# working.net
KiCad netlist of a schematic drawn in EAGLE
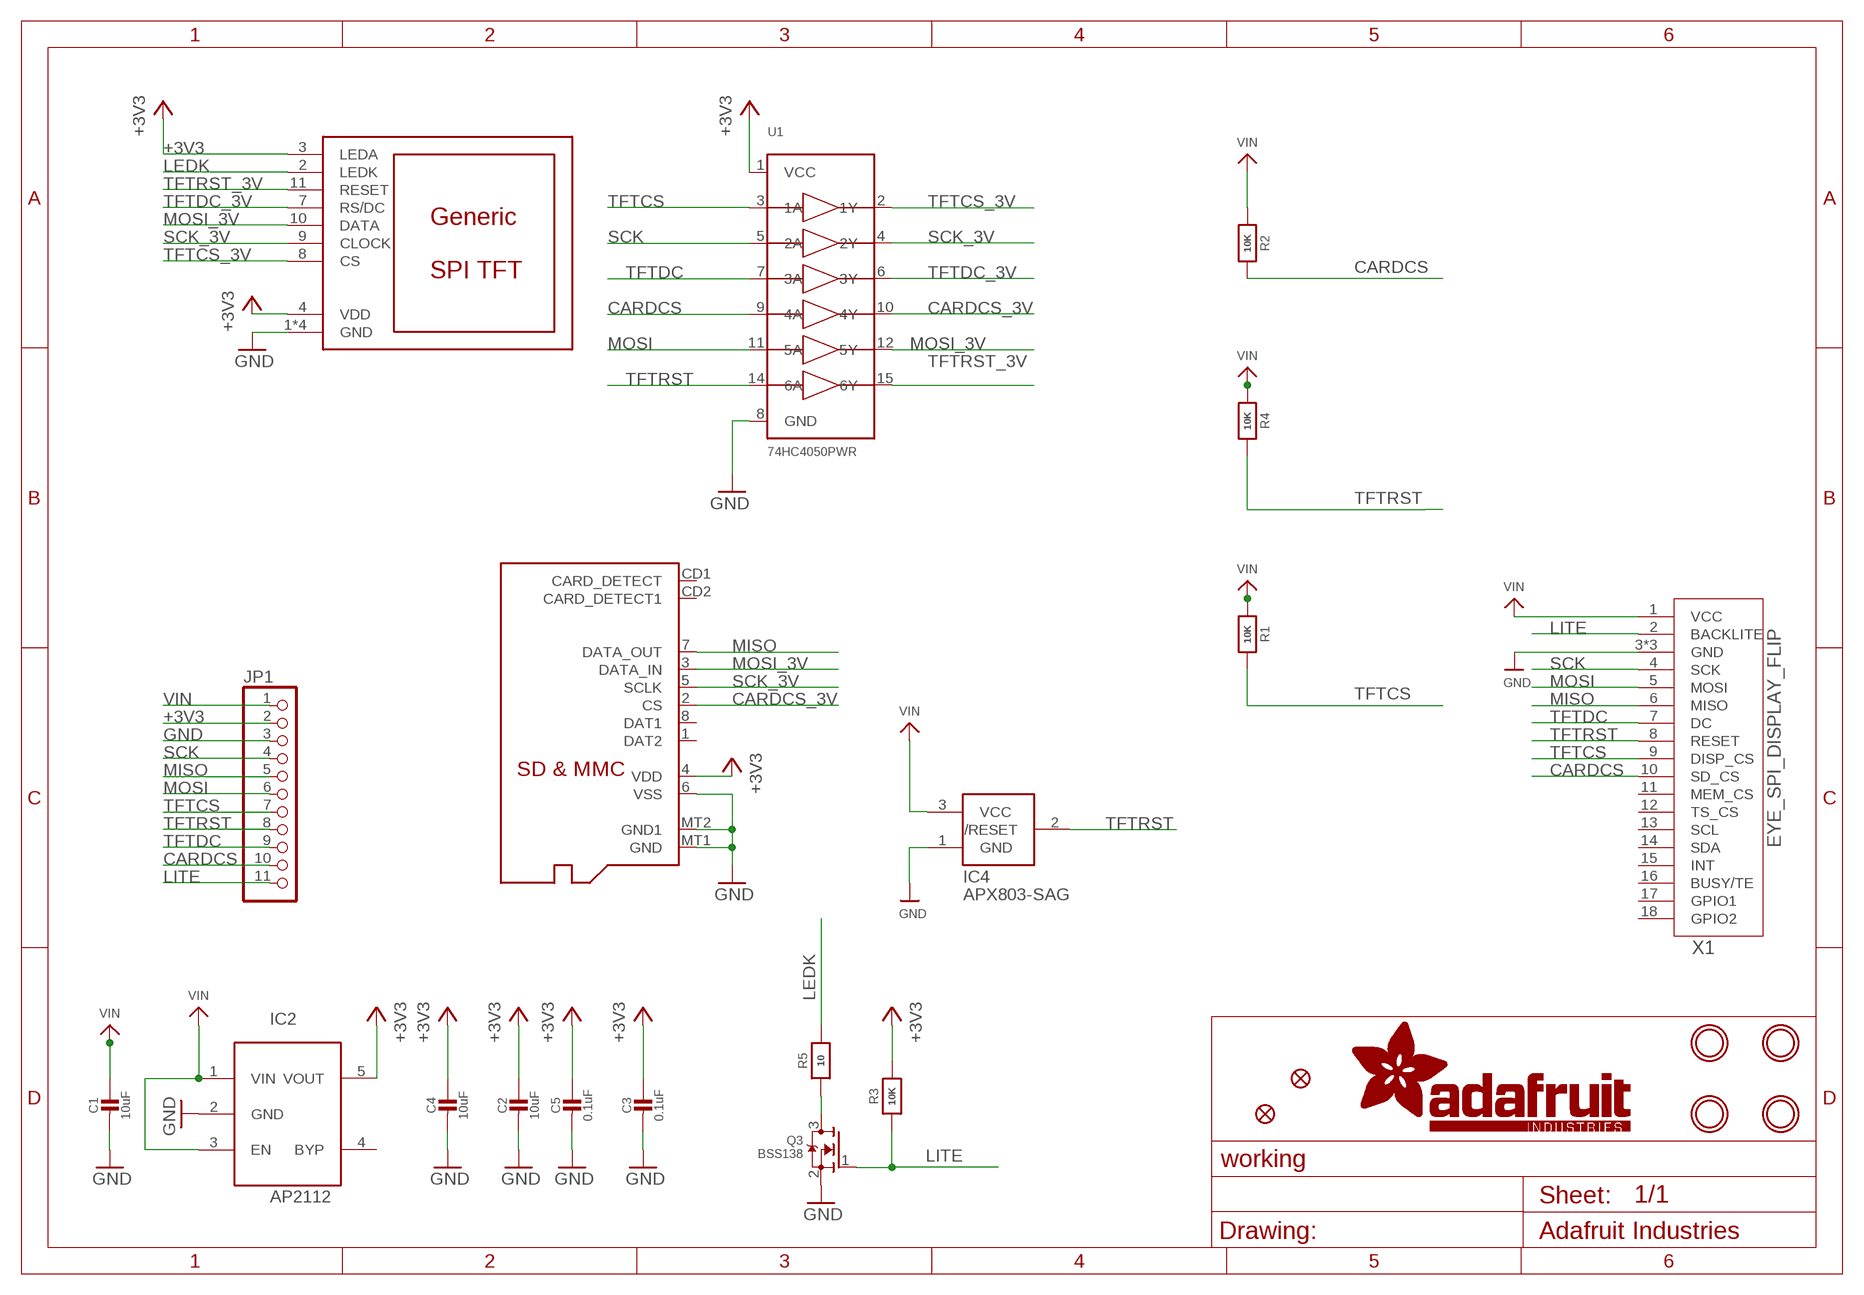
[diagram p0: schematic, sheet 1]

(export (version "E")
  (design (tool "Eeschema 10.0.6"))
  (components
    (comp (ref "C1")
      (value "10uF")
      (footprint "eagle-import:0805-NO")
      (libsource (lib "eagle-import") (part "CAP_CERAMIC0805-NOOUTLINE"))
    )
    (comp (ref "C2")
      (value "10uF")
      (footprint "eagle-import:0805-NO")
      (libsource (lib "eagle-import") (part "CAP_CERAMIC0805-NOOUTLINE"))
    )
    (comp (ref "C3")
      (value "0.1uF")
      (footprint "eagle-import:0603-NO")
      (libsource (lib "eagle-import") (part "CAP_CERAMIC0603_NO"))
    )
    (comp (ref "C4")
      (value "10uF")
      (footprint "eagle-import:0805-NO")
      (libsource (lib "eagle-import") (part "CAP_CERAMIC0805-NOOUTLINE"))
    )
    (comp (ref "C5")
      (value "0.1uF")
      (footprint "eagle-import:0603-NO")
      (libsource (lib "eagle-import") (part "CAP_CERAMIC0603_NO"))
    )
    (comp (ref "DISP1")
      (value "DISP_LCD_GENERIC_SPI_1.47IN_172X320_12P_WRAPUNDER")
      (footprint "eagle-import:TFT_1.47IN_172X320_12P")
      (libsource (lib "eagle-import") (part "DISP_LCD_GENERIC_SPI_1.47IN_172X320_12P_WRAPUNDER"))
    )
    (comp (ref "IC2")
      (value "AP2112")
      (footprint "eagle-import:SOT23-5L")
      (libsource (lib "eagle-import") (part "LP298XS"))
    )
    (comp (ref "IC4")
      (value "APX803-SAG")
      (footprint "eagle-import:SOT23")
      (libsource (lib "eagle-import") (part "AXP083-SAG"))
    )
    (comp (ref "JP1")
      (value "HEADER-1X1176MIL")
      (footprint "eagle-import:1X11_ROUND_76")
      (libsource (lib "eagle-import") (part "HEADER-1X1176MIL"))
    )
    (comp (ref "Q2")
      (value "MICROSD")
      (footprint "eagle-import:MICROSD")
      (libsource (lib "eagle-import") (part "MICROSD"))
    )
    (comp (ref "Q3")
      (value "BSS138")
      (footprint "eagle-import:SOT23-WIDE")
      (libsource (lib "eagle-import") (part "MOSFET-NWIDE"))
    )
    (comp (ref "R1")
      (value "10K")
      (footprint "eagle-import:0603-NO")
      (libsource (lib "eagle-import") (part "RESISTOR_0603_NOOUT"))
    )
    (comp (ref "R2")
      (value "10K")
      (footprint "eagle-import:0603-NO")
      (libsource (lib "eagle-import") (part "RESISTOR_0603_NOOUT"))
    )
    (comp (ref "R3")
      (value "10K")
      (footprint "eagle-import:0603-NO")
      (libsource (lib "eagle-import") (part "RESISTOR_0603_NOOUT"))
    )
    (comp (ref "R4")
      (value "10K")
      (footprint "eagle-import:0603-NO")
      (libsource (lib "eagle-import") (part "RESISTOR_0603_NOOUT"))
    )
    (comp (ref "R5")
      (value "10")
      (footprint "eagle-import:0603-NO")
      (libsource (lib "eagle-import") (part "RESISTOR_0603_NOOUT"))
    )
    (comp (ref "U$4")
      (value "FIDUCIAL_1MM")
      (footprint "eagle-import:FIDUCIAL_1MM")
      (libsource (lib "eagle-import") (part "FIDUCIAL_1MM"))
    )
    (comp (ref "U$5")
      (value "FIDUCIAL_1MM")
      (footprint "eagle-import:FIDUCIAL_1MM")
      (libsource (lib "eagle-import") (part "FIDUCIAL_1MM"))
    )
    (comp (ref "U$7")
      (value "MOUNTINGHOLE2.5")
      (footprint "eagle-import:MOUNTINGHOLE_2.5_PLATED")
      (libsource (lib "eagle-import") (part "MOUNTINGHOLE2.5"))
    )
    (comp (ref "U$8")
      (value "MOUNTINGHOLE2.5")
      (footprint "eagle-import:MOUNTINGHOLE_2.5_PLATED")
      (libsource (lib "eagle-import") (part "MOUNTINGHOLE2.5"))
    )
    (comp (ref "U$9")
      (value "MOUNTINGHOLE2.5")
      (footprint "eagle-import:MOUNTINGHOLE_2.5_PLATED")
      (libsource (lib "eagle-import") (part "MOUNTINGHOLE2.5"))
    )
    (comp (ref "U$10")
      (value "MOUNTINGHOLE2.5")
      (footprint "eagle-import:MOUNTINGHOLE_2.5_PLATED")
      (libsource (lib "eagle-import") (part "MOUNTINGHOLE2.5"))
    )
    (comp (ref "U1")
      (value "74HC4050PWR")
      (footprint "eagle-import:TSSOP16")
      (libsource (lib "eagle-import") (part "74HC4050DTSSOP"))
    )
    (comp (ref "X1")
      (value "EYE_SPI_DISPLAY_FLIP")
      (footprint "eagle-import:EYE_SPI_DISPLAY_BOTCONTACT")
      (libsource (lib "eagle-import") (part "EYE_SPI_DISPLAY_FLIP"))
    )
  )
  (nets
    (net (code "1") (name "+3V3") (class "Default")
      (node (ref "C2") (pin "1") (pinfunction "1_1") (pintype "passive"))
      (node (ref "C3") (pin "1") (pinfunction "1_1") (pintype "passive"))
      (node (ref "C4") (pin "1") (pinfunction "1_1") (pintype "passive"))
      (node (ref "C5") (pin "1") (pinfunction "1_1") (pintype "passive"))
      (node (ref "DISP1") (pin "3") (pinfunction "LEDA_3") (pintype "input"))
      (node (ref "DISP1") (pin "4") (pinfunction "VDD_4") (pintype "power_in"))
      (node (ref "IC2") (pin "5") (pinfunction "VOUT_5") (pintype "bidirectional"))
      (node (ref "JP1") (pin "2") (pinfunction "2_2") (pintype "passive"))
      (node (ref "Q2") (pin "4") (pinfunction "VDD_4") (pintype "power_in"))
      (node (ref "R3") (pin "2") (pinfunction "2_2") (pintype "passive"))
      (node (ref "U1") (pin "1") (pinfunction "VCC_1") (pintype "bidirectional"))
    )
    (net (code "2") (name "/CARDCS") (class "Default")
      (node (ref "JP1") (pin "10") (pinfunction "10_10") (pintype "passive"))
      (node (ref "R2") (pin "1") (pinfunction "1_1") (pintype "passive"))
      (node (ref "U1") (pin "9") (pinfunction "4A_9") (pintype "bidirectional"))
      (node (ref "X1") (pin "10") (pinfunction "SD_CS_10") (pintype "input"))
    )
    (net (code "3") (name "/CARDCS_3V") (class "Default")
      (node (ref "Q2") (pin "2") (pinfunction "CS_2") (pintype "input"))
      (node (ref "U1") (pin "10") (pinfunction "4Y_10") (pintype "bidirectional"))
    )
    (net (code "4") (name "/LEDK") (class "Default")
      (node (ref "DISP1") (pin "2") (pinfunction "LEDK_2") (pintype "input"))
      (node (ref "R5") (pin "2") (pinfunction "2_2") (pintype "passive"))
    )
    (net (code "5") (name "/LITE") (class "Default")
      (node (ref "JP1") (pin "11") (pinfunction "11_11") (pintype "passive"))
      (node (ref "Q3") (pin "1") (pinfunction "G_1") (pintype "bidirectional"))
      (node (ref "R3") (pin "1") (pinfunction "1_1") (pintype "passive"))
      (node (ref "X1") (pin "2") (pinfunction "BACKLITE_2") (pintype "input"))
    )
    (net (code "6") (name "/MISO") (class "Default")
      (node (ref "JP1") (pin "5") (pinfunction "5_5") (pintype "passive"))
      (node (ref "Q2") (pin "7") (pinfunction "DATA_OUT_7") (pintype "output"))
      (node (ref "X1") (pin "6") (pinfunction "MISO_6") (pintype "output"))
    )
    (net (code "7") (name "/MOSI") (class "Default")
      (node (ref "JP1") (pin "6") (pinfunction "6_6") (pintype "passive"))
      (node (ref "U1") (pin "11") (pinfunction "5A_11") (pintype "bidirectional"))
      (node (ref "X1") (pin "5") (pinfunction "MOSI_5") (pintype "input"))
    )
    (net (code "8") (name "/MOSI_3V") (class "Default")
      (node (ref "DISP1") (pin "10") (pinfunction "DATA_10") (pintype "bidirectional"))
      (node (ref "Q2") (pin "3") (pinfunction "DATA_IN_3") (pintype "input"))
      (node (ref "U1") (pin "12") (pinfunction "5Y_12") (pintype "bidirectional"))
    )
    (net (code "9") (name "/SCK") (class "Default")
      (node (ref "JP1") (pin "4") (pinfunction "4_4") (pintype "passive"))
      (node (ref "U1") (pin "5") (pinfunction "2A_5") (pintype "bidirectional"))
      (node (ref "X1") (pin "4") (pinfunction "SCK_4") (pintype "input"))
    )
    (net (code "10") (name "/SCK_3V") (class "Default")
      (node (ref "DISP1") (pin "9") (pinfunction "CLOCK_9") (pintype "input"))
      (node (ref "Q2") (pin "5") (pinfunction "SCLK_5") (pintype "input"))
      (node (ref "U1") (pin "4") (pinfunction "2Y_4") (pintype "bidirectional"))
    )
    (net (code "11") (name "/TFTCS") (class "Default")
      (node (ref "JP1") (pin "7") (pinfunction "7_7") (pintype "passive"))
      (node (ref "R1") (pin "1") (pinfunction "1_1") (pintype "passive"))
      (node (ref "U1") (pin "3") (pinfunction "1A_3") (pintype "bidirectional"))
      (node (ref "X1") (pin "9") (pinfunction "DISP_CS_9") (pintype "input"))
    )
    (net (code "12") (name "/TFTCS_3V") (class "Default")
      (node (ref "DISP1") (pin "8") (pinfunction "CS_8") (pintype "input"))
      (node (ref "U1") (pin "2") (pinfunction "1Y_2") (pintype "bidirectional"))
    )
    (net (code "13") (name "/TFTDC") (class "Default")
      (node (ref "JP1") (pin "9") (pinfunction "9_9") (pintype "passive"))
      (node (ref "U1") (pin "7") (pinfunction "3A_7") (pintype "bidirectional"))
      (node (ref "X1") (pin "7") (pinfunction "DC_7") (pintype "input"))
    )
    (net (code "14") (name "/TFTDC_3V") (class "Default")
      (node (ref "DISP1") (pin "7") (pinfunction "RS/DC_7") (pintype "input"))
      (node (ref "U1") (pin "6") (pinfunction "3Y_6") (pintype "bidirectional"))
    )
    (net (code "15") (name "/TFTRST") (class "Default")
      (node (ref "IC4") (pin "2") (pinfunction "/RESET_2") (pintype "output"))
      (node (ref "JP1") (pin "8") (pinfunction "8_8") (pintype "passive"))
      (node (ref "R4") (pin "1") (pinfunction "1_1") (pintype "passive"))
      (node (ref "U1") (pin "14") (pinfunction "6A_14") (pintype "bidirectional"))
      (node (ref "X1") (pin "8") (pinfunction "RESET_8") (pintype "input"))
    )
    (net (code "16") (name "/TFTRST_3V") (class "Default")
      (node (ref "DISP1") (pin "11") (pinfunction "RESET_11") (pintype "input"))
      (node (ref "U1") (pin "15") (pinfunction "6Y_15") (pintype "bidirectional"))
    )
    (net (code "17") (name "GND") (class "Default")
      (node (ref "C1") (pin "2") (pinfunction "2_2") (pintype "passive"))
      (node (ref "C2") (pin "2") (pinfunction "2_2") (pintype "passive"))
      (node (ref "C3") (pin "2") (pinfunction "2_2") (pintype "passive"))
      (node (ref "C4") (pin "2") (pinfunction "2_2") (pintype "passive"))
      (node (ref "C5") (pin "2") (pinfunction "2_2") (pintype "passive"))
      (node (ref "DISP1") (pin "1") (pinfunction "GND_1") (pintype "power_in"))
      (node (ref "DISP1") (pin "12") (pinfunction "GND_12") (pintype "power_in"))
      (node (ref "DISP1") (pin "5") (pinfunction "GND_5") (pintype "power_in"))
      (node (ref "DISP1") (pin "6") (pinfunction "GND_6") (pintype "power_in"))
      (node (ref "IC2") (pin "2") (pinfunction "GND_2") (pintype "bidirectional"))
      (node (ref "IC4") (pin "1") (pinfunction "GND_1") (pintype "power_in"))
      (node (ref "JP1") (pin "3") (pinfunction "3_3") (pintype "passive"))
      (node (ref "Q2") (pin "6") (pinfunction "VSS_6") (pintype "power_in"))
      (node (ref "Q2") (pin "MT1") (pinfunction "GND_MT1") (pintype "power_in"))
      (node (ref "Q2") (pin "MT2") (pinfunction "GND1_MT2") (pintype "power_in"))
      (node (ref "Q3") (pin "2") (pinfunction "S_2") (pintype "bidirectional"))
      (node (ref "U1") (pin "8") (pinfunction "GND_8") (pintype "bidirectional"))
      (node (ref "X1") (pin "3") (pinfunction "GND_3") (pintype "power_in"))
      (node (ref "X1") (pin "SUPPORT1") (pinfunction "GND_SUPPORT1") (pintype "power_in"))
      (node (ref "X1") (pin "SUPPORT2") (pinfunction "GND_SUPPORT2") (pintype "power_in"))
    )
    (net (code "18") (name "Net-(Q3-D)") (class "Default")
      (node (ref "Q3") (pin "3") (pinfunction "D_3") (pintype "bidirectional"))
      (node (ref "R5") (pin "1") (pinfunction "1_1") (pintype "passive"))
    )
    (net (code "19") (name "VIN") (class "Default")
      (node (ref "C1") (pin "1") (pinfunction "1_1") (pintype "passive"))
      (node (ref "IC2") (pin "1") (pinfunction "VIN_1") (pintype "bidirectional"))
      (node (ref "IC2") (pin "3") (pinfunction "EN_3") (pintype "bidirectional"))
      (node (ref "IC4") (pin "3") (pinfunction "VCC_3") (pintype "power_in"))
      (node (ref "JP1") (pin "1") (pinfunction "1_1") (pintype "passive"))
      (node (ref "R1") (pin "2") (pinfunction "2_2") (pintype "passive"))
      (node (ref "R2") (pin "2") (pinfunction "2_2") (pintype "passive"))
      (node (ref "R4") (pin "2") (pinfunction "2_2") (pintype "passive"))
      (node (ref "X1") (pin "1") (pinfunction "VCC_1") (pintype "power_in"))
    )
    (net (code "20") (name "unconnected-(IC2-BYP-Pad4)") (class "Default")
      (node (ref "IC2") (pin "4") (pinfunction "BYP_4") (pintype "bidirectional"))
    )
    (net (code "21") (name "unconnected-(Q2-CARD_DETECT-PadCD1)") (class "Default")
      (node (ref "Q2") (pin "CD1") (pinfunction "CARD_DETECT_CD1") (pintype "passive"))
    )
    (net (code "22") (name "unconnected-(Q2-CARD_DETECT1-PadCD2)") (class "Default")
      (node (ref "Q2") (pin "CD2") (pinfunction "CARD_DETECT1_CD2") (pintype "passive"))
    )
    (net (code "23") (name "unconnected-(Q2-DAT1-Pad8)") (class "Default")
      (node (ref "Q2") (pin "8") (pinfunction "DAT1_8") (pintype "bidirectional"))
    )
    (net (code "24") (name "unconnected-(Q2-DAT2-Pad1)") (class "Default")
      (node (ref "Q2") (pin "1") (pinfunction "DAT2_1") (pintype "bidirectional"))
    )
    (net (code "25") (name "unconnected-(X1-BUSY{slash}TE-Pad16)") (class "Default")
      (node (ref "X1") (pin "16") (pinfunction "BUSY/TE_16") (pintype "output"))
    )
    (net (code "26") (name "unconnected-(X1-GPIO1-Pad17)") (class "Default")
      (node (ref "X1") (pin "17") (pinfunction "GPIO1_17") (pintype "passive"))
    )
    (net (code "27") (name "unconnected-(X1-GPIO2-Pad18)") (class "Default")
      (node (ref "X1") (pin "18") (pinfunction "GPIO2_18") (pintype "passive"))
    )
    (net (code "28") (name "unconnected-(X1-INT-Pad15)") (class "Default")
      (node (ref "X1") (pin "15") (pinfunction "INT_15") (pintype "output"))
    )
    (net (code "29") (name "unconnected-(X1-MEM_CS-Pad11)") (class "Default")
      (node (ref "X1") (pin "11") (pinfunction "MEM_CS_11") (pintype "input"))
    )
    (net (code "30") (name "unconnected-(X1-SCL-Pad13)") (class "Default")
      (node (ref "X1") (pin "13") (pinfunction "SCL_13") (pintype "input"))
    )
    (net (code "31") (name "unconnected-(X1-SDA-Pad14)") (class "Default")
      (node (ref "X1") (pin "14") (pinfunction "SDA_14") (pintype "bidirectional"))
    )
    (net (code "32") (name "unconnected-(X1-TS_CS-Pad12)") (class "Default")
      (node (ref "X1") (pin "12") (pinfunction "TS_CS_12") (pintype "input"))
    )
  )
)
